# Nixie_Pin_Out_Board_v1_0_1.net
KiCad netlist of a schematic drawn in EAGLE
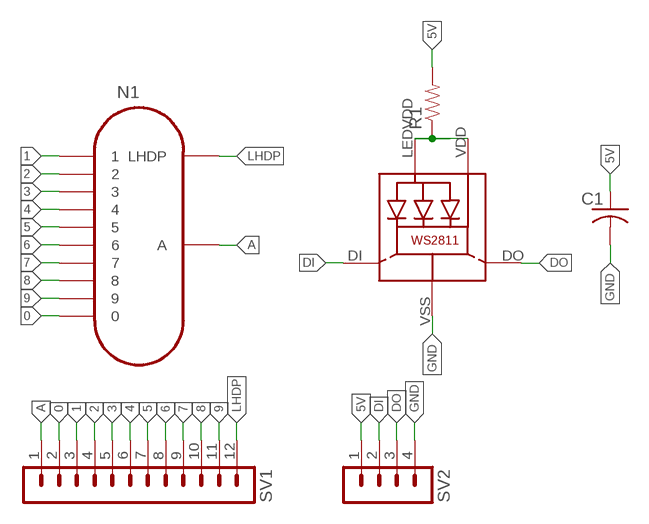
[diagram p0: schematic, sheet 1]

(export (version "E")
  (design (tool "Eeschema 10.0.6"))
  (components
    (comp (ref "C1")
      (value "C-USC0805K")
      (footprint "eagle-import:C0805K")
      (libsource (lib "eagle-import") (part "C-USC0805K"))
    )
    (comp (ref "LED1")
      (value "WS28115050")
      (footprint "eagle-import:WS28115050")
      (libsource (lib "eagle-import") (part "WS28115050"))
    )
    (comp (ref "N1")
      (value "IN-12B")
      (footprint "eagle-import:IN-12")
      (libsource (lib "eagle-import") (part "IN-12B"))
    )
    (comp (ref "R1")
      (value "RESISTOR0805-RES")
      (footprint "eagle-import:0805")
      (libsource (lib "eagle-import") (part "RESISTOR0805-RES"))
    )
    (comp (ref "SV1")
      (value "MA12-1")
      (footprint "eagle-import:MA12-1")
      (libsource (lib "eagle-import") (part "MA12-1"))
    )
    (comp (ref "SV2")
      (value "MA04-1")
      (footprint "eagle-import:MA04-1")
      (libsource (lib "eagle-import") (part "MA04-1"))
    )
  )
  (nets
    (net (code "1") (name "0") (class "Default")
      (node (ref "N1") (pin "0") (pinfunction "0_0") (pintype "bidirectional"))
      (node (ref "SV1") (pin "2") (pinfunction "2_2") (pintype "passive"))
    )
    (net (code "2") (name "1") (class "Default")
      (node (ref "N1") (pin "1") (pinfunction "1_1") (pintype "bidirectional"))
      (node (ref "SV1") (pin "3") (pinfunction "3_3") (pintype "passive"))
    )
    (net (code "3") (name "2") (class "Default")
      (node (ref "N1") (pin "2") (pinfunction "2_2") (pintype "bidirectional"))
      (node (ref "SV1") (pin "4") (pinfunction "4_4") (pintype "passive"))
    )
    (net (code "4") (name "3") (class "Default")
      (node (ref "N1") (pin "3") (pinfunction "3_3") (pintype "bidirectional"))
      (node (ref "SV1") (pin "5") (pinfunction "5_5") (pintype "passive"))
    )
    (net (code "5") (name "4") (class "Default")
      (node (ref "N1") (pin "4") (pinfunction "4_4") (pintype "bidirectional"))
      (node (ref "SV1") (pin "6") (pinfunction "6_6") (pintype "passive"))
    )
    (net (code "6") (name "5") (class "Default")
      (node (ref "N1") (pin "5") (pinfunction "5_5") (pintype "bidirectional"))
      (node (ref "SV1") (pin "7") (pinfunction "7_7") (pintype "passive"))
    )
    (net (code "7") (name "5V") (class "Default")
      (node (ref "C1") (pin "1") (pinfunction "1_1") (pintype "passive"))
      (node (ref "R1") (pin "2") (pinfunction "2_2") (pintype "passive"))
      (node (ref "SV2") (pin "1") (pinfunction "1_1") (pintype "passive"))
    )
    (net (code "8") (name "6") (class "Default")
      (node (ref "N1") (pin "6") (pinfunction "6_6") (pintype "bidirectional"))
      (node (ref "SV1") (pin "8") (pinfunction "8_8") (pintype "passive"))
    )
    (net (code "9") (name "7") (class "Default")
      (node (ref "N1") (pin "7") (pinfunction "7_7") (pintype "bidirectional"))
      (node (ref "SV1") (pin "9") (pinfunction "9_9") (pintype "passive"))
    )
    (net (code "10") (name "8") (class "Default")
      (node (ref "N1") (pin "8") (pinfunction "8_8") (pintype "bidirectional"))
      (node (ref "SV1") (pin "10") (pinfunction "10_10") (pintype "passive"))
    )
    (net (code "11") (name "9") (class "Default")
      (node (ref "N1") (pin "9") (pinfunction "9_9") (pintype "bidirectional"))
      (node (ref "SV1") (pin "11") (pinfunction "11_11") (pintype "passive"))
    )
    (net (code "12") (name "A") (class "Default")
      (node (ref "N1") (pin "A") (pinfunction "A_A") (pintype "bidirectional"))
      (node (ref "SV1") (pin "1") (pinfunction "1_1") (pintype "passive"))
    )
    (net (code "13") (name "DI") (class "Default")
      (node (ref "LED1") (pin "DI") (pinfunction "DI_DI") (pintype "input"))
      (node (ref "SV2") (pin "2") (pinfunction "2_2") (pintype "passive"))
    )
    (net (code "14") (name "DO") (class "Default")
      (node (ref "LED1") (pin "DO") (pinfunction "DO_DO") (pintype "output"))
      (node (ref "SV2") (pin "3") (pinfunction "3_3") (pintype "passive"))
    )
    (net (code "15") (name "GND") (class "Default")
      (node (ref "C1") (pin "2") (pinfunction "2_2") (pintype "passive"))
      (node (ref "LED1") (pin "VSS") (pinfunction "GND_VSS") (pintype "power_in"))
      (node (ref "SV2") (pin "4") (pinfunction "4_4") (pintype "passive"))
    )
    (net (code "16") (name "LHDP") (class "Default")
      (node (ref "N1") (pin "LHDP") (pinfunction "LHDP_LHDP") (pintype "bidirectional"))
      (node (ref "SV1") (pin "12") (pinfunction "12_12") (pintype "passive"))
    )
    (net (code "17") (name "Net-(LED1-PadLEDVDD)") (class "Default")
      (node (ref "LED1") (pin "LEDVDD") (pinfunction "LEDVDD_LEDVDD") (pintype "power_in"))
      (node (ref "LED1") (pin "VDD") (pinfunction "VDD_VDD") (pintype "power_in"))
      (node (ref "R1") (pin "1") (pinfunction "1_1") (pintype "passive"))
    )
  )
)
